# 27-mitosis.net
KiCad netlist of a schematic drawn in Altium Designer
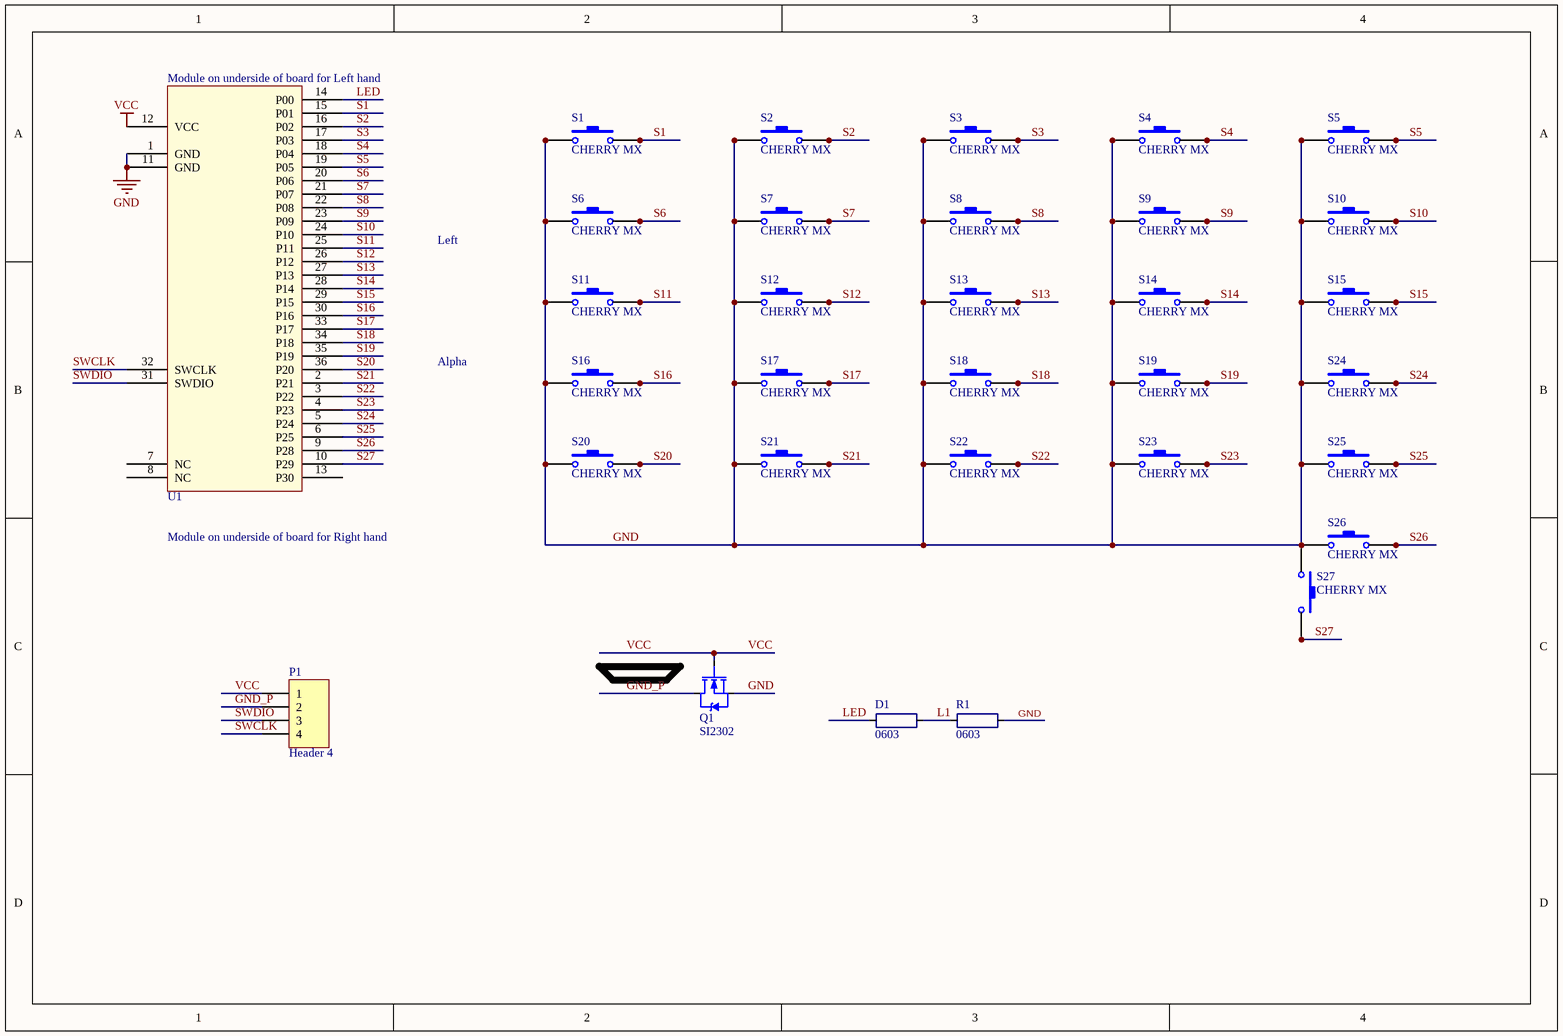
[diagram p0: 27-mitosis.SchDoc]

(export (version "E")
  (design (tool "Eeschema 10.0.6"))
  (components
    (comp (ref "D1") (value "0603") (footprint "RESC2012X06N") (libsource (lib "SK") (part "0603")))
    (comp (ref "P1")
      (value "Header 4")
      (footprint "HDR1X4")
      (description "Header, 4-Pin")
      (fields (field (name "PUBLISHER") "Altium Limited"))
      (libsource (lib "Miscellaneous Connectors") (part "Header 4"))
    )
    (comp (ref "Q1")
      (value "SI2302")
      (footprint "SOT-23")
      (description "N-Channel Logic MOSFET")
      (fields (field (name "PUBLISHER") "Altium Limited"))
      (libsource (lib "SK") (part "SI2302"))
    )
    (comp (ref "R1") (value "0603") (footprint "RESC2012X06N") (libsource (lib "SK") (part "0603")))
    (comp (ref "S1")
      (value "CHERRY MX")
      (footprint "cherry")
      (description "Switch")
      (fields (field (name "PUBLISHER") "Altium Limited"))
      (libsource (lib "SK") (part "CHERRY MX"))
    )
    (comp (ref "S2")
      (value "CHERRY MX")
      (footprint "cherry")
      (description "Switch")
      (fields (field (name "PUBLISHER") "Altium Limited"))
      (libsource (lib "SK") (part "CHERRY MX"))
    )
    (comp (ref "S3")
      (value "CHERRY MX")
      (footprint "cherry")
      (description "Switch")
      (fields (field (name "PUBLISHER") "Altium Limited"))
      (libsource (lib "SK") (part "CHERRY MX"))
    )
    (comp (ref "S4")
      (value "CHERRY MX")
      (footprint "cherry")
      (description "Switch")
      (fields (field (name "PUBLISHER") "Altium Limited"))
      (libsource (lib "SK") (part "CHERRY MX"))
    )
    (comp (ref "S5")
      (value "CHERRY MX")
      (footprint "cherry")
      (description "Switch")
      (fields (field (name "PUBLISHER") "Altium Limited"))
      (libsource (lib "SK") (part "CHERRY MX"))
    )
    (comp (ref "S6")
      (value "CHERRY MX")
      (footprint "cherry")
      (description "Switch")
      (fields (field (name "PUBLISHER") "Altium Limited"))
      (libsource (lib "SK") (part "CHERRY MX"))
    )
    (comp (ref "S7")
      (value "CHERRY MX")
      (footprint "cherry")
      (description "Switch")
      (fields (field (name "PUBLISHER") "Altium Limited"))
      (libsource (lib "SK") (part "CHERRY MX"))
    )
    (comp (ref "S8")
      (value "CHERRY MX")
      (footprint "cherry")
      (description "Switch")
      (fields (field (name "PUBLISHER") "Altium Limited"))
      (libsource (lib "SK") (part "CHERRY MX"))
    )
    (comp (ref "S9")
      (value "CHERRY MX")
      (footprint "cherry")
      (description "Switch")
      (fields (field (name "PUBLISHER") "Altium Limited"))
      (libsource (lib "SK") (part "CHERRY MX"))
    )
    (comp (ref "S10")
      (value "CHERRY MX")
      (footprint "cherry")
      (description "Switch")
      (fields (field (name "PUBLISHER") "Altium Limited"))
      (libsource (lib "SK") (part "CHERRY MX"))
    )
    (comp (ref "S11")
      (value "CHERRY MX")
      (footprint "cherry")
      (description "Switch")
      (fields (field (name "PUBLISHER") "Altium Limited"))
      (libsource (lib "SK") (part "CHERRY MX"))
    )
    (comp (ref "S12")
      (value "CHERRY MX")
      (footprint "cherry")
      (description "Switch")
      (fields (field (name "PUBLISHER") "Altium Limited"))
      (libsource (lib "SK") (part "CHERRY MX"))
    )
    (comp (ref "S13")
      (value "CHERRY MX")
      (footprint "cherry")
      (description "Switch")
      (fields (field (name "PUBLISHER") "Altium Limited"))
      (libsource (lib "SK") (part "CHERRY MX"))
    )
    (comp (ref "S14")
      (value "CHERRY MX")
      (footprint "cherry")
      (description "Switch")
      (fields (field (name "PUBLISHER") "Altium Limited"))
      (libsource (lib "SK") (part "CHERRY MX"))
    )
    (comp (ref "S15")
      (value "CHERRY MX")
      (footprint "cherry")
      (description "Switch")
      (fields (field (name "PUBLISHER") "Altium Limited"))
      (libsource (lib "SK") (part "CHERRY MX"))
    )
    (comp (ref "S16")
      (value "CHERRY MX")
      (footprint "cherry")
      (description "Switch")
      (fields (field (name "PUBLISHER") "Altium Limited"))
      (libsource (lib "SK") (part "CHERRY MX"))
    )
    (comp (ref "S17")
      (value "CHERRY MX")
      (footprint "cherry")
      (description "Switch")
      (fields (field (name "PUBLISHER") "Altium Limited"))
      (libsource (lib "SK") (part "CHERRY MX"))
    )
    (comp (ref "S18")
      (value "CHERRY MX")
      (footprint "cherry")
      (description "Switch")
      (fields (field (name "PUBLISHER") "Altium Limited"))
      (libsource (lib "SK") (part "CHERRY MX"))
    )
    (comp (ref "S19")
      (value "CHERRY MX")
      (footprint "cherry")
      (description "Switch")
      (fields (field (name "PUBLISHER") "Altium Limited"))
      (libsource (lib "SK") (part "CHERRY MX"))
    )
    (comp (ref "S20")
      (value "CHERRY MX")
      (footprint "cherry")
      (description "Switch")
      (fields (field (name "PUBLISHER") "Altium Limited"))
      (libsource (lib "SK") (part "CHERRY MX"))
    )
    (comp (ref "S21")
      (value "CHERRY MX")
      (footprint "cherry")
      (description "Switch")
      (fields (field (name "PUBLISHER") "Altium Limited"))
      (libsource (lib "SK") (part "CHERRY MX"))
    )
    (comp (ref "S22")
      (value "CHERRY MX")
      (footprint "cherry")
      (description "Switch")
      (fields (field (name "PUBLISHER") "Altium Limited"))
      (libsource (lib "SK") (part "CHERRY MX"))
    )
    (comp (ref "S23")
      (value "CHERRY MX")
      (footprint "cherry")
      (description "Switch")
      (fields (field (name "PUBLISHER") "Altium Limited"))
      (libsource (lib "SK") (part "CHERRY MX"))
    )
    (comp (ref "S24")
      (value "CHERRY MX")
      (footprint "cherry")
      (description "Switch")
      (fields (field (name "PUBLISHER") "Altium Limited"))
      (libsource (lib "mitosis") (part "CHERRY MX"))
    )
    (comp (ref "S25")
      (value "CHERRY MX")
      (footprint "cherry")
      (description "Switch")
      (fields (field (name "PUBLISHER") "Altium Limited"))
      (libsource (lib "mitosis") (part "CHERRY MX"))
    )
    (comp (ref "S26")
      (value "CHERRY MX")
      (footprint "cherry")
      (description "Switch")
      (fields (field (name "PUBLISHER") "Altium Limited"))
      (libsource (lib "mitosis") (part "CHERRY MX"))
    )
    (comp (ref "S27")
      (value "CHERRY MX")
      (footprint "cherry")
      (description "Switch")
      (fields (field (name "PUBLISHER") "Altium Limited"))
      (libsource (lib "mitosis") (part "CHERRY MX"))
    )
    (comp (ref "U1")
      (value "Core51822 (B)")
      (footprint "Core51822 (B)")
      (description "NRF51822 (B)")
      (libsource (lib "SK") (part "Core51822 (B)"))
    )
  )
  (nets
    (net (code "1") (name "/GND_P") (class "Default")
      (node (ref "P1") (pin "2") (pinfunction "2_2") (pintype "passive"))
      (node (ref "Q1") (pin "3") (pinfunction "D_3") (pintype "passive"))
    )
    (net (code "2") (name "/L1") (class "Default")
      (node (ref "D1") (pin "1") (pinfunction "1_1") (pintype "passive"))
      (node (ref "R1") (pin "2") (pinfunction "2_2") (pintype "passive"))
    )
    (net (code "3") (name "/LED") (class "Default")
      (node (ref "D1") (pin "2") (pinfunction "2_2") (pintype "passive"))
      (node (ref "U1") (pin "14") (pinfunction "P00_14") (pintype "passive"))
    )
    (net (code "4") (name "/S1") (class "Default")
      (node (ref "S1") (pin "10") (pinfunction "10_10") (pintype "passive"))
      (node (ref "S1") (pin "12") (pinfunction "12_12") (pintype "passive"))
      (node (ref "S1") (pin "2") (pinfunction "2_2") (pintype "passive"))
      (node (ref "S1") (pin "4") (pinfunction "4_4") (pintype "passive"))
      (node (ref "S1") (pin "6") (pinfunction "6_6") (pintype "passive"))
      (node (ref "S1") (pin "8") (pinfunction "8_8") (pintype "passive"))
      (node (ref "U1") (pin "15") (pinfunction "P01_15") (pintype "passive"))
    )
    (net (code "5") (name "/S2") (class "Default")
      (node (ref "S2") (pin "10") (pinfunction "10_10") (pintype "passive"))
      (node (ref "S2") (pin "12") (pinfunction "12_12") (pintype "passive"))
      (node (ref "S2") (pin "2") (pinfunction "2_2") (pintype "passive"))
      (node (ref "S2") (pin "4") (pinfunction "4_4") (pintype "passive"))
      (node (ref "S2") (pin "6") (pinfunction "6_6") (pintype "passive"))
      (node (ref "S2") (pin "8") (pinfunction "8_8") (pintype "passive"))
      (node (ref "U1") (pin "16") (pinfunction "P02_16") (pintype "passive"))
    )
    (net (code "6") (name "/S3") (class "Default")
      (node (ref "S3") (pin "10") (pinfunction "10_10") (pintype "passive"))
      (node (ref "S3") (pin "12") (pinfunction "12_12") (pintype "passive"))
      (node (ref "S3") (pin "2") (pinfunction "2_2") (pintype "passive"))
      (node (ref "S3") (pin "4") (pinfunction "4_4") (pintype "passive"))
      (node (ref "S3") (pin "6") (pinfunction "6_6") (pintype "passive"))
      (node (ref "S3") (pin "8") (pinfunction "8_8") (pintype "passive"))
      (node (ref "U1") (pin "17") (pinfunction "P03_17") (pintype "passive"))
    )
    (net (code "7") (name "/S4") (class "Default")
      (node (ref "S4") (pin "10") (pinfunction "10_10") (pintype "passive"))
      (node (ref "S4") (pin "12") (pinfunction "12_12") (pintype "passive"))
      (node (ref "S4") (pin "2") (pinfunction "2_2") (pintype "passive"))
      (node (ref "S4") (pin "4") (pinfunction "4_4") (pintype "passive"))
      (node (ref "S4") (pin "6") (pinfunction "6_6") (pintype "passive"))
      (node (ref "S4") (pin "8") (pinfunction "8_8") (pintype "passive"))
      (node (ref "U1") (pin "18") (pinfunction "P04_18") (pintype "passive"))
    )
    (net (code "8") (name "/S5") (class "Default")
      (node (ref "S5") (pin "10") (pinfunction "10_10") (pintype "passive"))
      (node (ref "S5") (pin "12") (pinfunction "12_12") (pintype "passive"))
      (node (ref "S5") (pin "2") (pinfunction "2_2") (pintype "passive"))
      (node (ref "S5") (pin "4") (pinfunction "4_4") (pintype "passive"))
      (node (ref "S5") (pin "6") (pinfunction "6_6") (pintype "passive"))
      (node (ref "S5") (pin "8") (pinfunction "8_8") (pintype "passive"))
      (node (ref "U1") (pin "19") (pinfunction "P05_19") (pintype "passive"))
    )
    (net (code "9") (name "/S6") (class "Default")
      (node (ref "S6") (pin "10") (pinfunction "10_10") (pintype "passive"))
      (node (ref "S6") (pin "12") (pinfunction "12_12") (pintype "passive"))
      (node (ref "S6") (pin "2") (pinfunction "2_2") (pintype "passive"))
      (node (ref "S6") (pin "4") (pinfunction "4_4") (pintype "passive"))
      (node (ref "S6") (pin "6") (pinfunction "6_6") (pintype "passive"))
      (node (ref "S6") (pin "8") (pinfunction "8_8") (pintype "passive"))
      (node (ref "U1") (pin "20") (pinfunction "P06_20") (pintype "passive"))
    )
    (net (code "10") (name "/S7") (class "Default")
      (node (ref "S7") (pin "10") (pinfunction "10_10") (pintype "passive"))
      (node (ref "S7") (pin "12") (pinfunction "12_12") (pintype "passive"))
      (node (ref "S7") (pin "2") (pinfunction "2_2") (pintype "passive"))
      (node (ref "S7") (pin "4") (pinfunction "4_4") (pintype "passive"))
      (node (ref "S7") (pin "6") (pinfunction "6_6") (pintype "passive"))
      (node (ref "S7") (pin "8") (pinfunction "8_8") (pintype "passive"))
      (node (ref "U1") (pin "21") (pinfunction "P07_21") (pintype "passive"))
    )
    (net (code "11") (name "/S8") (class "Default")
      (node (ref "S8") (pin "10") (pinfunction "10_10") (pintype "passive"))
      (node (ref "S8") (pin "12") (pinfunction "12_12") (pintype "passive"))
      (node (ref "S8") (pin "2") (pinfunction "2_2") (pintype "passive"))
      (node (ref "S8") (pin "4") (pinfunction "4_4") (pintype "passive"))
      (node (ref "S8") (pin "6") (pinfunction "6_6") (pintype "passive"))
      (node (ref "S8") (pin "8") (pinfunction "8_8") (pintype "passive"))
      (node (ref "U1") (pin "22") (pinfunction "P08_22") (pintype "passive"))
    )
    (net (code "12") (name "/S9") (class "Default")
      (node (ref "S9") (pin "10") (pinfunction "10_10") (pintype "passive"))
      (node (ref "S9") (pin "12") (pinfunction "12_12") (pintype "passive"))
      (node (ref "S9") (pin "2") (pinfunction "2_2") (pintype "passive"))
      (node (ref "S9") (pin "4") (pinfunction "4_4") (pintype "passive"))
      (node (ref "S9") (pin "6") (pinfunction "6_6") (pintype "passive"))
      (node (ref "S9") (pin "8") (pinfunction "8_8") (pintype "passive"))
      (node (ref "U1") (pin "23") (pinfunction "P09_23") (pintype "passive"))
    )
    (net (code "13") (name "/S10") (class "Default")
      (node (ref "S10") (pin "10") (pinfunction "10_10") (pintype "passive"))
      (node (ref "S10") (pin "12") (pinfunction "12_12") (pintype "passive"))
      (node (ref "S10") (pin "2") (pinfunction "2_2") (pintype "passive"))
      (node (ref "S10") (pin "4") (pinfunction "4_4") (pintype "passive"))
      (node (ref "S10") (pin "6") (pinfunction "6_6") (pintype "passive"))
      (node (ref "S10") (pin "8") (pinfunction "8_8") (pintype "passive"))
      (node (ref "U1") (pin "24") (pinfunction "P10_24") (pintype "passive"))
    )
    (net (code "14") (name "/S11") (class "Default")
      (node (ref "S11") (pin "10") (pinfunction "10_10") (pintype "passive"))
      (node (ref "S11") (pin "12") (pinfunction "12_12") (pintype "passive"))
      (node (ref "S11") (pin "2") (pinfunction "2_2") (pintype "passive"))
      (node (ref "S11") (pin "4") (pinfunction "4_4") (pintype "passive"))
      (node (ref "S11") (pin "6") (pinfunction "6_6") (pintype "passive"))
      (node (ref "S11") (pin "8") (pinfunction "8_8") (pintype "passive"))
      (node (ref "U1") (pin "25") (pinfunction "P11_25") (pintype "passive"))
    )
    (net (code "15") (name "/S12") (class "Default")
      (node (ref "S12") (pin "10") (pinfunction "10_10") (pintype "passive"))
      (node (ref "S12") (pin "12") (pinfunction "12_12") (pintype "passive"))
      (node (ref "S12") (pin "2") (pinfunction "2_2") (pintype "passive"))
      (node (ref "S12") (pin "4") (pinfunction "4_4") (pintype "passive"))
      (node (ref "S12") (pin "6") (pinfunction "6_6") (pintype "passive"))
      (node (ref "S12") (pin "8") (pinfunction "8_8") (pintype "passive"))
      (node (ref "U1") (pin "26") (pinfunction "P12_26") (pintype "passive"))
    )
    (net (code "16") (name "/S13") (class "Default")
      (node (ref "S13") (pin "10") (pinfunction "10_10") (pintype "passive"))
      (node (ref "S13") (pin "12") (pinfunction "12_12") (pintype "passive"))
      (node (ref "S13") (pin "2") (pinfunction "2_2") (pintype "passive"))
      (node (ref "S13") (pin "4") (pinfunction "4_4") (pintype "passive"))
      (node (ref "S13") (pin "6") (pinfunction "6_6") (pintype "passive"))
      (node (ref "S13") (pin "8") (pinfunction "8_8") (pintype "passive"))
      (node (ref "U1") (pin "27") (pinfunction "P13_27") (pintype "passive"))
    )
    (net (code "17") (name "/S14") (class "Default")
      (node (ref "S14") (pin "10") (pinfunction "10_10") (pintype "passive"))
      (node (ref "S14") (pin "12") (pinfunction "12_12") (pintype "passive"))
      (node (ref "S14") (pin "2") (pinfunction "2_2") (pintype "passive"))
      (node (ref "S14") (pin "4") (pinfunction "4_4") (pintype "passive"))
      (node (ref "S14") (pin "6") (pinfunction "6_6") (pintype "passive"))
      (node (ref "S14") (pin "8") (pinfunction "8_8") (pintype "passive"))
      (node (ref "U1") (pin "28") (pinfunction "P14_28") (pintype "passive"))
    )
    (net (code "18") (name "/S15") (class "Default")
      (node (ref "S15") (pin "10") (pinfunction "10_10") (pintype "passive"))
      (node (ref "S15") (pin "12") (pinfunction "12_12") (pintype "passive"))
      (node (ref "S15") (pin "2") (pinfunction "2_2") (pintype "passive"))
      (node (ref "S15") (pin "4") (pinfunction "4_4") (pintype "passive"))
      (node (ref "S15") (pin "6") (pinfunction "6_6") (pintype "passive"))
      (node (ref "S15") (pin "8") (pinfunction "8_8") (pintype "passive"))
      (node (ref "U1") (pin "29") (pinfunction "P15_29") (pintype "passive"))
    )
    (net (code "19") (name "/S16") (class "Default")
      (node (ref "S16") (pin "10") (pinfunction "10_10") (pintype "passive"))
      (node (ref "S16") (pin "12") (pinfunction "12_12") (pintype "passive"))
      (node (ref "S16") (pin "2") (pinfunction "2_2") (pintype "passive"))
      (node (ref "S16") (pin "4") (pinfunction "4_4") (pintype "passive"))
      (node (ref "S16") (pin "6") (pinfunction "6_6") (pintype "passive"))
      (node (ref "S16") (pin "8") (pinfunction "8_8") (pintype "passive"))
      (node (ref "U1") (pin "30") (pinfunction "P16_30") (pintype "passive"))
    )
    (net (code "20") (name "/S17") (class "Default")
      (node (ref "S17") (pin "10") (pinfunction "10_10") (pintype "passive"))
      (node (ref "S17") (pin "12") (pinfunction "12_12") (pintype "passive"))
      (node (ref "S17") (pin "2") (pinfunction "2_2") (pintype "passive"))
      (node (ref "S17") (pin "4") (pinfunction "4_4") (pintype "passive"))
      (node (ref "S17") (pin "6") (pinfunction "6_6") (pintype "passive"))
      (node (ref "S17") (pin "8") (pinfunction "8_8") (pintype "passive"))
      (node (ref "U1") (pin "33") (pinfunction "P17_33") (pintype "passive"))
    )
    (net (code "21") (name "/S18") (class "Default")
      (node (ref "S18") (pin "10") (pinfunction "10_10") (pintype "passive"))
      (node (ref "S18") (pin "12") (pinfunction "12_12") (pintype "passive"))
      (node (ref "S18") (pin "2") (pinfunction "2_2") (pintype "passive"))
      (node (ref "S18") (pin "4") (pinfunction "4_4") (pintype "passive"))
      (node (ref "S18") (pin "6") (pinfunction "6_6") (pintype "passive"))
      (node (ref "S18") (pin "8") (pinfunction "8_8") (pintype "passive"))
      (node (ref "U1") (pin "34") (pinfunction "P18_34") (pintype "passive"))
    )
    (net (code "22") (name "/S19") (class "Default")
      (node (ref "S19") (pin "10") (pinfunction "10_10") (pintype "passive"))
      (node (ref "S19") (pin "12") (pinfunction "12_12") (pintype "passive"))
      (node (ref "S19") (pin "2") (pinfunction "2_2") (pintype "passive"))
      (node (ref "S19") (pin "4") (pinfunction "4_4") (pintype "passive"))
      (node (ref "S19") (pin "6") (pinfunction "6_6") (pintype "passive"))
      (node (ref "S19") (pin "8") (pinfunction "8_8") (pintype "passive"))
      (node (ref "U1") (pin "35") (pinfunction "P19_35") (pintype "passive"))
    )
    (net (code "23") (name "/S20") (class "Default")
      (node (ref "S20") (pin "10") (pinfunction "10_10") (pintype "passive"))
      (node (ref "S20") (pin "12") (pinfunction "12_12") (pintype "passive"))
      (node (ref "S20") (pin "2") (pinfunction "2_2") (pintype "passive"))
      (node (ref "S20") (pin "4") (pinfunction "4_4") (pintype "passive"))
      (node (ref "S20") (pin "6") (pinfunction "6_6") (pintype "passive"))
      (node (ref "S20") (pin "8") (pinfunction "8_8") (pintype "passive"))
      (node (ref "U1") (pin "36") (pinfunction "P20_36") (pintype "passive"))
    )
    (net (code "24") (name "/S21") (class "Default")
      (node (ref "S21") (pin "10") (pinfunction "10_10") (pintype "passive"))
      (node (ref "S21") (pin "12") (pinfunction "12_12") (pintype "passive"))
      (node (ref "S21") (pin "2") (pinfunction "2_2") (pintype "passive"))
      (node (ref "S21") (pin "4") (pinfunction "4_4") (pintype "passive"))
      (node (ref "S21") (pin "6") (pinfunction "6_6") (pintype "passive"))
      (node (ref "S21") (pin "8") (pinfunction "8_8") (pintype "passive"))
      (node (ref "U1") (pin "2") (pinfunction "P21_2") (pintype "passive"))
    )
    (net (code "25") (name "/S22") (class "Default")
      (node (ref "S22") (pin "10") (pinfunction "10_10") (pintype "passive"))
      (node (ref "S22") (pin "12") (pinfunction "12_12") (pintype "passive"))
      (node (ref "S22") (pin "2") (pinfunction "2_2") (pintype "passive"))
      (node (ref "S22") (pin "4") (pinfunction "4_4") (pintype "passive"))
      (node (ref "S22") (pin "6") (pinfunction "6_6") (pintype "passive"))
      (node (ref "S22") (pin "8") (pinfunction "8_8") (pintype "passive"))
      (node (ref "U1") (pin "3") (pinfunction "P22_3") (pintype "passive"))
    )
    (net (code "26") (name "/S23") (class "Default")
      (node (ref "S23") (pin "10") (pinfunction "10_10") (pintype "passive"))
      (node (ref "S23") (pin "12") (pinfunction "12_12") (pintype "passive"))
      (node (ref "S23") (pin "2") (pinfunction "2_2") (pintype "passive"))
      (node (ref "S23") (pin "4") (pinfunction "4_4") (pintype "passive"))
      (node (ref "S23") (pin "6") (pinfunction "6_6") (pintype "passive"))
      (node (ref "S23") (pin "8") (pinfunction "8_8") (pintype "passive"))
      (node (ref "U1") (pin "4") (pinfunction "P23_4") (pintype "passive"))
    )
    (net (code "27") (name "/S24") (class "Default")
      (node (ref "S24") (pin "10") (pinfunction "10_10") (pintype "passive"))
      (node (ref "S24") (pin "12") (pinfunction "12_12") (pintype "passive"))
      (node (ref "S24") (pin "2") (pinfunction "2_2") (pintype "passive"))
      (node (ref "S24") (pin "4") (pinfunction "4_4") (pintype "passive"))
      (node (ref "S24") (pin "6") (pinfunction "6_6") (pintype "passive"))
      (node (ref "S24") (pin "8") (pinfunction "8_8") (pintype "passive"))
      (node (ref "U1") (pin "5") (pinfunction "P24_5") (pintype "passive"))
    )
    (net (code "28") (name "/S25") (class "Default")
      (node (ref "S25") (pin "10") (pinfunction "10_10") (pintype "passive"))
      (node (ref "S25") (pin "12") (pinfunction "12_12") (pintype "passive"))
      (node (ref "S25") (pin "2") (pinfunction "2_2") (pintype "passive"))
      (node (ref "S25") (pin "4") (pinfunction "4_4") (pintype "passive"))
      (node (ref "S25") (pin "6") (pinfunction "6_6") (pintype "passive"))
      (node (ref "S25") (pin "8") (pinfunction "8_8") (pintype "passive"))
      (node (ref "U1") (pin "6") (pinfunction "P25_6") (pintype "passive"))
    )
    (net (code "29") (name "/S26") (class "Default")
      (node (ref "S26") (pin "10") (pinfunction "10_10") (pintype "passive"))
      (node (ref "S26") (pin "12") (pinfunction "12_12") (pintype "passive"))
      (node (ref "S26") (pin "2") (pinfunction "2_2") (pintype "passive"))
      (node (ref "S26") (pin "4") (pinfunction "4_4") (pintype "passive"))
      (node (ref "S26") (pin "6") (pinfunction "6_6") (pintype "passive"))
      (node (ref "S26") (pin "8") (pinfunction "8_8") (pintype "passive"))
      (node (ref "U1") (pin "9") (pinfunction "P28_9") (pintype "passive"))
    )
    (net (code "30") (name "/S27") (class "Default")
      (node (ref "S27") (pin "10") (pinfunction "10_10") (pintype "passive"))
      (node (ref "S27") (pin "12") (pinfunction "12_12") (pintype "passive"))
      (node (ref "S27") (pin "2") (pinfunction "2_2") (pintype "passive"))
      (node (ref "S27") (pin "4") (pinfunction "4_4") (pintype "passive"))
      (node (ref "S27") (pin "6") (pinfunction "6_6") (pintype "passive"))
      (node (ref "S27") (pin "8") (pinfunction "8_8") (pintype "passive"))
      (node (ref "U1") (pin "10") (pinfunction "P29_10") (pintype "passive"))
    )
    (net (code "31") (name "/SWCLK") (class "Default")
      (node (ref "P1") (pin "4") (pinfunction "4_4") (pintype "passive"))
      (node (ref "U1") (pin "32") (pinfunction "SWCLK_32") (pintype "passive"))
    )
    (net (code "32") (name "/SWDIO") (class "Default")
      (node (ref "P1") (pin "3") (pinfunction "3_3") (pintype "passive"))
      (node (ref "U1") (pin "31") (pinfunction "SWDIO_31") (pintype "passive"))
    )
    (net (code "33") (name "GND") (class "Default")
      (node (ref "Q1") (pin "2") (pinfunction "S_2") (pintype "passive"))
      (node (ref "R1") (pin "1") (pinfunction "1_1") (pintype "passive"))
      (node (ref "S1") (pin "1") (pinfunction "1_1") (pintype "passive"))
      (node (ref "S1") (pin "11") (pinfunction "11_11") (pintype "passive"))
      (node (ref "S1") (pin "3") (pinfunction "3_3") (pintype "passive"))
      (node (ref "S1") (pin "5") (pinfunction "5_5") (pintype "passive"))
      (node (ref "S1") (pin "7") (pinfunction "7_7") (pintype "passive"))
      (node (ref "S1") (pin "9") (pinfunction "9_9") (pintype "passive"))
      (node (ref "S10") (pin "1") (pinfunction "1_1") (pintype "passive"))
      (node (ref "S10") (pin "11") (pinfunction "11_11") (pintype "passive"))
      (node (ref "S10") (pin "3") (pinfunction "3_3") (pintype "passive"))
      (node (ref "S10") (pin "5") (pinfunction "5_5") (pintype "passive"))
      (node (ref "S10") (pin "7") (pinfunction "7_7") (pintype "passive"))
      (node (ref "S10") (pin "9") (pinfunction "9_9") (pintype "passive"))
      (node (ref "S11") (pin "1") (pinfunction "1_1") (pintype "passive"))
      (node (ref "S11") (pin "11") (pinfunction "11_11") (pintype "passive"))
      (node (ref "S11") (pin "3") (pinfunction "3_3") (pintype "passive"))
      (node (ref "S11") (pin "5") (pinfunction "5_5") (pintype "passive"))
      (node (ref "S11") (pin "7") (pinfunction "7_7") (pintype "passive"))
      (node (ref "S11") (pin "9") (pinfunction "9_9") (pintype "passive"))
      (node (ref "S12") (pin "1") (pinfunction "1_1") (pintype "passive"))
      (node (ref "S12") (pin "11") (pinfunction "11_11") (pintype "passive"))
      (node (ref "S12") (pin "3") (pinfunction "3_3") (pintype "passive"))
      (node (ref "S12") (pin "5") (pinfunction "5_5") (pintype "passive"))
      (node (ref "S12") (pin "7") (pinfunction "7_7") (pintype "passive"))
      (node (ref "S12") (pin "9") (pinfunction "9_9") (pintype "passive"))
      (node (ref "S13") (pin "1") (pinfunction "1_1") (pintype "passive"))
      (node (ref "S13") (pin "11") (pinfunction "11_11") (pintype "passive"))
      (node (ref "S13") (pin "3") (pinfunction "3_3") (pintype "passive"))
      (node (ref "S13") (pin "5") (pinfunction "5_5") (pintype "passive"))
      (node (ref "S13") (pin "7") (pinfunction "7_7") (pintype "passive"))
      (node (ref "S13") (pin "9") (pinfunction "9_9") (pintype "passive"))
      (node (ref "S14") (pin "1") (pinfunction "1_1") (pintype "passive"))
      (node (ref "S14") (pin "11") (pinfunction "11_11") (pintype "passive"))
      (node (ref "S14") (pin "3") (pinfunction "3_3") (pintype "passive"))
      (node (ref "S14") (pin "5") (pinfunction "5_5") (pintype "passive"))
      (node (ref "S14") (pin "7") (pinfunction "7_7") (pintype "passive"))
      (node (ref "S14") (pin "9") (pinfunction "9_9") (pintype "passive"))
      (node (ref "S15") (pin "1") (pinfunction "1_1") (pintype "passive"))
      (node (ref "S15") (pin "11") (pinfunction "11_11") (pintype "passive"))
      (node (ref "S15") (pin "3") (pinfunction "3_3") (pintype "passive"))
      (node (ref "S15") (pin "5") (pinfunction "5_5") (pintype "passive"))
      (node (ref "S15") (pin "7") (pinfunction "7_7") (pintype "passive"))
      (node (ref "S15") (pin "9") (pinfunction "9_9") (pintype "passive"))
      (node (ref "S16") (pin "1") (pinfunction "1_1") (pintype "passive"))
      (node (ref "S16") (pin "11") (pinfunction "11_11") (pintype "passive"))
      (node (ref "S16") (pin "3") (pinfunction "3_3") (pintype "passive"))
      (node (ref "S16") (pin "5") (pinfunction "5_5") (pintype "passive"))
      (node (ref "S16") (pin "7") (pinfunction "7_7") (pintype "passive"))
      (node (ref "S16") (pin "9") (pinfunction "9_9") (pintype "passive"))
      (node (ref "S17") (pin "1") (pinfunction "1_1") (pintype "passive"))
      (node (ref "S17") (pin "11") (pinfunction "11_11") (pintype "passive"))
      (node (ref "S17") (pin "3") (pinfunction "3_3") (pintype "passive"))
      (node (ref "S17") (pin "5") (pinfunction "5_5") (pintype "passive"))
      (node (ref "S17") (pin "7") (pinfunction "7_7") (pintype "passive"))
      (node (ref "S17") (pin "9") (pinfunction "9_9") (pintype "passive"))
      (node (ref "S18") (pin "1") (pinfunction "1_1") (pintype "passive"))
      (node (ref "S18") (pin "11") (pinfunction "11_11") (pintype "passive"))
      (node (ref "S18") (pin "3") (pinfunction "3_3") (pintype "passive"))
      (node (ref "S18") (pin "5") (pinfunction "5_5") (pintype "passive"))
      (node (ref "S18") (pin "7") (pinfunction "7_7") (pintype "passive"))
      (node (ref "S18") (pin "9") (pinfunction "9_9") (pintype "passive"))
      (node (ref "S19") (pin "1") (pinfunction "1_1") (pintype "passive"))
      (node (ref "S19") (pin "11") (pinfunction "11_11") (pintype "passive"))
      (node (ref "S19") (pin "3") (pinfunction "3_3") (pintype "passive"))
      (node (ref "S19") (pin "5") (pinfunction "5_5") (pintype "passive"))
      (node (ref "S19") (pin "7") (pinfunction "7_7") (pintype "passive"))
      (node (ref "S19") (pin "9") (pinfunction "9_9") (pintype "passive"))
      (node (ref "S2") (pin "1") (pinfunction "1_1") (pintype "passive"))
      (node (ref "S2") (pin "11") (pinfunction "11_11") (pintype "passive"))
      (node (ref "S2") (pin "3") (pinfunction "3_3") (pintype "passive"))
      (node (ref "S2") (pin "5") (pinfunction "5_5") (pintype "passive"))
      (node (ref "S2") (pin "7") (pinfunction "7_7") (pintype "passive"))
      (node (ref "S2") (pin "9") (pinfunction "9_9") (pintype "passive"))
      (node (ref "S20") (pin "1") (pinfunction "1_1") (pintype "passive"))
      (node (ref "S20") (pin "11") (pinfunction "11_11") (pintype "passive"))
      (node (ref "S20") (pin "3") (pinfunction "3_3") (pintype "passive"))
      (node (ref "S20") (pin "5") (pinfunction "5_5") (pintype "passive"))
      (node (ref "S20") (pin "7") (pinfunction "7_7") (pintype "passive"))
      (node (ref "S20") (pin "9") (pinfunction "9_9") (pintype "passive"))
      (node (ref "S21") (pin "1") (pinfunction "1_1") (pintype "passive"))
      (node (ref "S21") (pin "11") (pinfunction "11_11") (pintype "passive"))
      (node (ref "S21") (pin "3") (pinfunction "3_3") (pintype "passive"))
      (node (ref "S21") (pin "5") (pinfunction "5_5") (pintype "passive"))
      (node (ref "S21") (pin "7") (pinfunction "7_7") (pintype "passive"))
      (node (ref "S21") (pin "9") (pinfunction "9_9") (pintype "passive"))
      (node (ref "S22") (pin "1") (pinfunction "1_1") (pintype "passive"))
      (node (ref "S22") (pin "11") (pinfunction "11_11") (pintype "passive"))
      (node (ref "S22") (pin "3") (pinfunction "3_3") (pintype "passive"))
      (node (ref "S22") (pin "5") (pinfunction "5_5") (pintype "passive"))
      (node (ref "S22") (pin "7") (pinfunction "7_7") (pintype "passive"))
      (node (ref "S22") (pin "9") (pinfunction "9_9") (pintype "passive"))
      (node (ref "S23") (pin "1") (pinfunction "1_1") (pintype "passive"))
      (node (ref "S23") (pin "11") (pinfunction "11_11") (pintype "passive"))
      (node (ref "S23") (pin "3") (pinfunction "3_3") (pintype "passive"))
      (node (ref "S23") (pin "5") (pinfunction "5_5") (pintype "passive"))
      (node (ref "S23") (pin "7") (pinfunction "7_7") (pintype "passive"))
      (node (ref "S23") (pin "9") (pinfunction "9_9") (pintype "passive"))
      (node (ref "S24") (pin "1") (pinfunction "1_1") (pintype "passive"))
      (node (ref "S24") (pin "11") (pinfunction "11_11") (pintype "passive"))
      (node (ref "S24") (pin "3") (pinfunction "3_3") (pintype "passive"))
      (node (ref "S24") (pin "5") (pinfunction "5_5") (pintype "passive"))
      (node (ref "S24") (pin "7") (pinfunction "7_7") (pintype "passive"))
      (node (ref "S24") (pin "9") (pinfunction "9_9") (pintype "passive"))
      (node (ref "S25") (pin "1") (pinfunction "1_1") (pintype "passive"))
      (node (ref "S25") (pin "11") (pinfunction "11_11") (pintype "passive"))
      (node (ref "S25") (pin "3") (pinfunction "3_3") (pintype "passive"))
      (node (ref "S25") (pin "5") (pinfunction "5_5") (pintype "passive"))
      (node (ref "S25") (pin "7") (pinfunction "7_7") (pintype "passive"))
      (node (ref "S25") (pin "9") (pinfunction "9_9") (pintype "passive"))
      (node (ref "S26") (pin "1") (pinfunction "1_1") (pintype "passive"))
      (node (ref "S26") (pin "11") (pinfunction "11_11") (pintype "passive"))
      (node (ref "S26") (pin "3") (pinfunction "3_3") (pintype "passive"))
      (node (ref "S26") (pin "5") (pinfunction "5_5") (pintype "passive"))
      (node (ref "S26") (pin "7") (pinfunction "7_7") (pintype "passive"))
      (node (ref "S26") (pin "9") (pinfunction "9_9") (pintype "passive"))
      (node (ref "S27") (pin "1") (pinfunction "1_1") (pintype "passive"))
      (node (ref "S27") (pin "11") (pinfunction "11_11") (pintype "passive"))
      (node (ref "S27") (pin "3") (pinfunction "3_3") (pintype "passive"))
      (node (ref "S27") (pin "5") (pinfunction "5_5") (pintype "passive"))
      (node (ref "S27") (pin "7") (pinfunction "7_7") (pintype "passive"))
      (node (ref "S27") (pin "9") (pinfunction "9_9") (pintype "passive"))
      (node (ref "S3") (pin "1") (pinfunction "1_1") (pintype "passive"))
      (node (ref "S3") (pin "11") (pinfunction "11_11") (pintype "passive"))
      (node (ref "S3") (pin "3") (pinfunction "3_3") (pintype "passive"))
      (node (ref "S3") (pin "5") (pinfunction "5_5") (pintype "passive"))
      (node (ref "S3") (pin "7") (pinfunction "7_7") (pintype "passive"))
      (node (ref "S3") (pin "9") (pinfunction "9_9") (pintype "passive"))
      (node (ref "S4") (pin "1") (pinfunction "1_1") (pintype "passive"))
      (node (ref "S4") (pin "11") (pinfunction "11_11") (pintype "passive"))
      (node (ref "S4") (pin "3") (pinfunction "3_3") (pintype "passive"))
      (node (ref "S4") (pin "5") (pinfunction "5_5") (pintype "passive"))
      (node (ref "S4") (pin "7") (pinfunction "7_7") (pintype "passive"))
      (node (ref "S4") (pin "9") (pinfunction "9_9") (pintype "passive"))
      (node (ref "S5") (pin "1") (pinfunction "1_1") (pintype "passive"))
      (node (ref "S5") (pin "11") (pinfunction "11_11") (pintype "passive"))
      (node (ref "S5") (pin "3") (pinfunction "3_3") (pintype "passive"))
      (node (ref "S5") (pin "5") (pinfunction "5_5") (pintype "passive"))
      (node (ref "S5") (pin "7") (pinfunction "7_7") (pintype "passive"))
      (node (ref "S5") (pin "9") (pinfunction "9_9") (pintype "passive"))
      (node (ref "S6") (pin "1") (pinfunction "1_1") (pintype "passive"))
      (node (ref "S6") (pin "11") (pinfunction "11_11") (pintype "passive"))
      (node (ref "S6") (pin "3") (pinfunction "3_3") (pintype "passive"))
      (node (ref "S6") (pin "5") (pinfunction "5_5") (pintype "passive"))
      (node (ref "S6") (pin "7") (pinfunction "7_7") (pintype "passive"))
      (node (ref "S6") (pin "9") (pinfunction "9_9") (pintype "passive"))
      (node (ref "S7") (pin "1") (pinfunction "1_1") (pintype "passive"))
      (node (ref "S7") (pin "11") (pinfunction "11_11") (pintype "passive"))
      (node (ref "S7") (pin "3") (pinfunction "3_3") (pintype "passive"))
      (node (ref "S7") (pin "5") (pinfunction "5_5") (pintype "passive"))
      (node (ref "S7") (pin "7") (pinfunction "7_7") (pintype "passive"))
      (node (ref "S7") (pin "9") (pinfunction "9_9") (pintype "passive"))
      (node (ref "S8") (pin "1") (pinfunction "1_1") (pintype "passive"))
      (node (ref "S8") (pin "11") (pinfunction "11_11") (pintype "passive"))
      (node (ref "S8") (pin "3") (pinfunction "3_3") (pintype "passive"))
      (node (ref "S8") (pin "5") (pinfunction "5_5") (pintype "passive"))
      (node (ref "S8") (pin "7") (pinfunction "7_7") (pintype "passive"))
      (node (ref "S8") (pin "9") (pinfunction "9_9") (pintype "passive"))
      (node (ref "S9") (pin "1") (pinfunction "1_1") (pintype "passive"))
      (node (ref "S9") (pin "11") (pinfunction "11_11") (pintype "passive"))
      (node (ref "S9") (pin "3") (pinfunction "3_3") (pintype "passive"))
      (node (ref "S9") (pin "5") (pinfunction "5_5") (pintype "passive"))
      (node (ref "S9") (pin "7") (pinfunction "7_7") (pintype "passive"))
      (node (ref "S9") (pin "9") (pinfunction "9_9") (pintype "passive"))
      (node (ref "U1") (pin "1") (pinfunction "GND_1") (pintype "passive"))
      (node (ref "U1") (pin "11") (pinfunction "GND_11") (pintype "passive"))
    )
    (net (code "34") (name "VCC") (class "Default")
      (node (ref "P1") (pin "1") (pinfunction "1_1") (pintype "passive"))
      (node (ref "Q1") (pin "1") (pinfunction "G_1") (pintype "passive"))
      (node (ref "U1") (pin "12") (pinfunction "VCC_12") (pintype "passive"))
    )
    (net (code "35") (name "unconnected-(U1-NC-Pad7)") (class "Default")
      (node (ref "U1") (pin "7") (pinfunction "NC_7") (pintype "passive"))
    )
    (net (code "36") (name "unconnected-(U1-NC-Pad8)") (class "Default")
      (node (ref "U1") (pin "8") (pinfunction "NC_8") (pintype "passive"))
    )
    (net (code "37") (name "unconnected-(U1-P30-Pad13)") (class "Default")
      (node (ref "U1") (pin "13") (pinfunction "P30_13") (pintype "passive"))
    )
  )
)
